# usb_isolated_uart_x2.net
KiCad netlist of a schematic drawn in Altium Designer
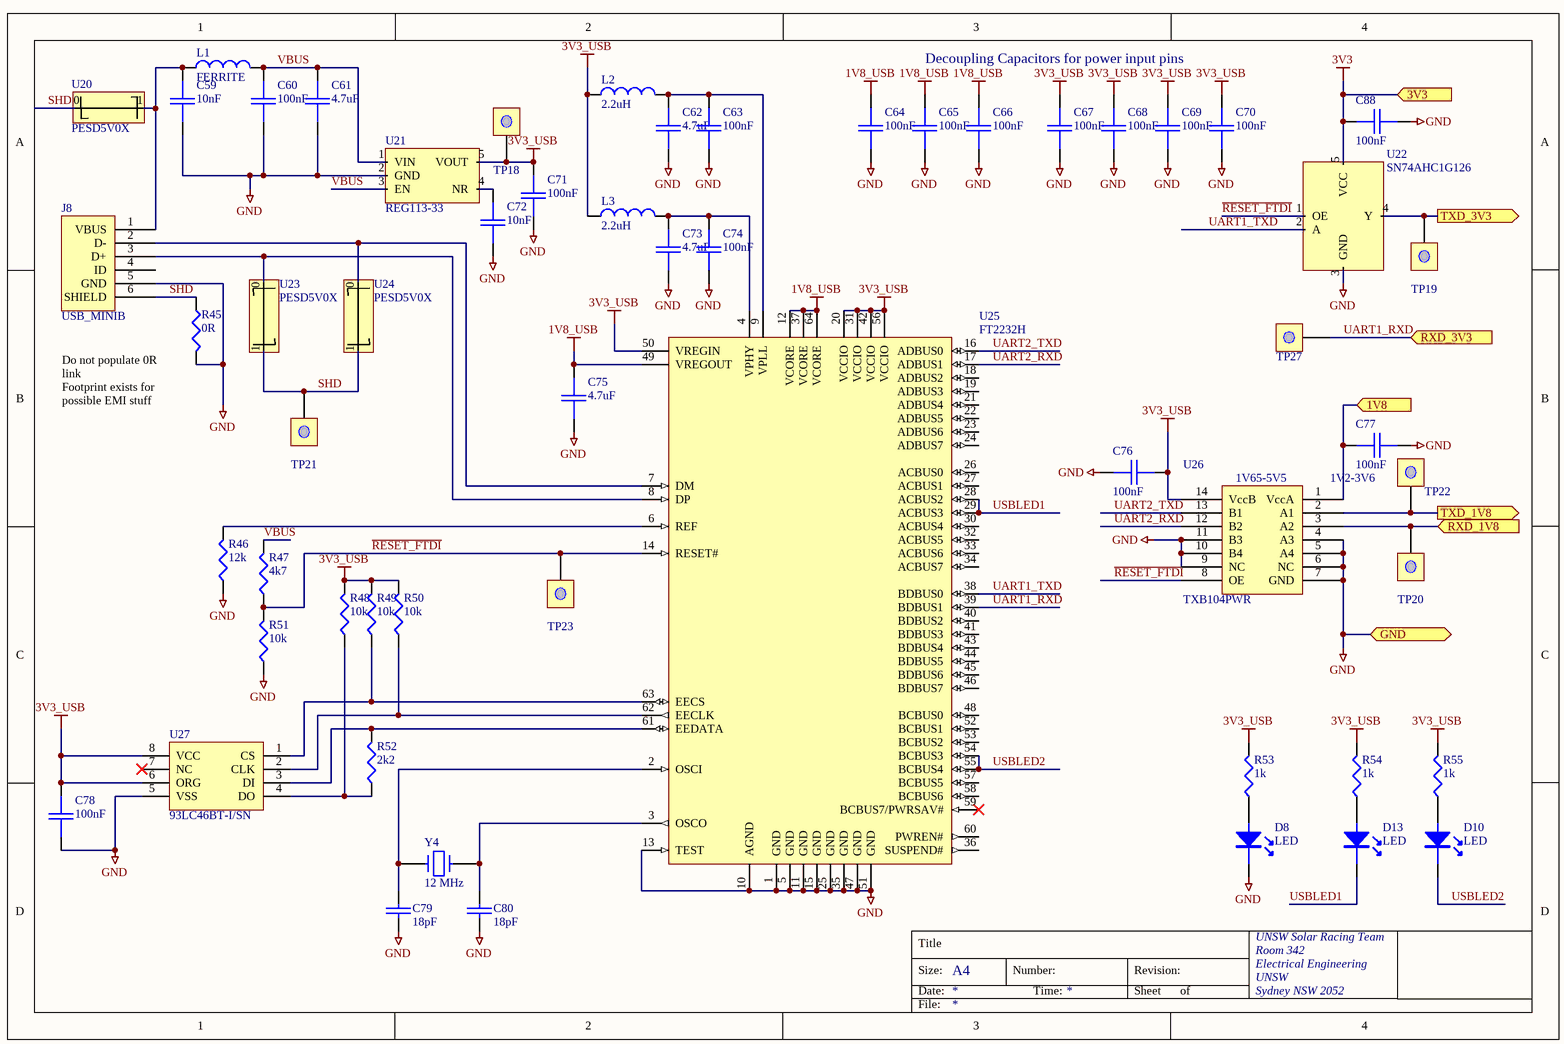
[diagram p0: usb_isolated_uart_x2.SchDoc]

(export (version "E")
  (design (tool "Eeschema 10.0.6"))
  (components
    (comp (ref "C59")
      (value "10nF")
      (footprint "0603")
      (description "Capacitor")
      (libsource (lib "RCLDQ") (part "CAP"))
    )
    (comp (ref "C60")
      (value "100nF")
      (footprint "0603")
      (description "Capacitor")
      (libsource (lib "RCLDQ") (part "CAP"))
    )
    (comp (ref "C61")
      (value "4.7uF")
      (footprint "0603")
      (description "Capacitor")
      (libsource (lib "RCLDQ") (part "CAP"))
    )
    (comp (ref "C62")
      (value "4.7uF")
      (footprint "0603")
      (description "Capacitor")
      (libsource (lib "RCLDQ") (part "CAP"))
    )
    (comp (ref "C63")
      (value "100nF")
      (footprint "0603")
      (description "Capacitor")
      (libsource (lib "RCLDQ") (part "CAP"))
    )
    (comp (ref "C64")
      (value "100nF")
      (footprint "0603")
      (description "Capacitor")
      (libsource (lib "RCLDQ") (part "CAP"))
    )
    (comp (ref "C65")
      (value "100nF")
      (footprint "0603")
      (description "Capacitor")
      (libsource (lib "RCLDQ") (part "CAP"))
    )
    (comp (ref "C66")
      (value "100nF")
      (footprint "0603")
      (description "Capacitor")
      (libsource (lib "RCLDQ") (part "CAP"))
    )
    (comp (ref "C67")
      (value "100nF")
      (footprint "0603")
      (description "Capacitor")
      (libsource (lib "RCLDQ") (part "CAP"))
    )
    (comp (ref "C68")
      (value "100nF")
      (footprint "0603")
      (description "Capacitor")
      (libsource (lib "RCLDQ") (part "CAP"))
    )
    (comp (ref "C69")
      (value "100nF")
      (footprint "0603")
      (description "Capacitor")
      (libsource (lib "RCLDQ") (part "CAP"))
    )
    (comp (ref "C70")
      (value "100nF")
      (footprint "0603")
      (description "Capacitor")
      (libsource (lib "RCLDQ") (part "CAP"))
    )
    (comp (ref "C71")
      (value "100nF")
      (footprint "0603")
      (description "Capacitor")
      (libsource (lib "RCLDQ") (part "CAP"))
    )
    (comp (ref "C72")
      (value "10nF")
      (footprint "0603")
      (description "Capacitor")
      (libsource (lib "RCLDQ") (part "CAP"))
    )
    (comp (ref "C73")
      (value "4.7uF")
      (footprint "0603")
      (description "Capacitor")
      (libsource (lib "RCLDQ") (part "CAP"))
    )
    (comp (ref "C74")
      (value "100nF")
      (footprint "0603")
      (description "Capacitor")
      (libsource (lib "RCLDQ") (part "CAP"))
    )
    (comp (ref "C75")
      (value "4.7uF")
      (footprint "0603")
      (description "Capacitor")
      (libsource (lib "RCLDQ") (part "CAP"))
    )
    (comp (ref "C76")
      (value "100nF")
      (footprint "0603")
      (description "Capacitor")
      (libsource (lib "RCLDQ") (part "CAP"))
    )
    (comp (ref "C77")
      (value "100nF")
      (footprint "0603")
      (description "Capacitor")
      (libsource (lib "RCLDQ") (part "CAP"))
    )
    (comp (ref "C78")
      (value "100nF")
      (footprint "0603")
      (description "Capacitor")
      (libsource (lib "RCLDQ") (part "CAP"))
    )
    (comp (ref "C79")
      (value "18pF")
      (footprint "0603")
      (description "Capacitor")
      (libsource (lib "*") (part "CAP"))
    )
    (comp (ref "C80")
      (value "18pF")
      (footprint "0603")
      (description "Capacitor")
      (libsource (lib "*") (part "CAP"))
    )
    (comp (ref "C88")
      (value "100nF")
      (footprint "0603")
      (description "Capacitor")
      (libsource (lib "RCLDQ") (part "CAP"))
    )
    (comp (ref "D8") (value "LED") (footprint "0805LED") (libsource (lib "RCLDQ") (part "LED")))
    (comp (ref "D10") (value "LED") (footprint "0805LED") (libsource (lib "RCLDQ") (part "LED")))
    (comp (ref "D13") (value "LED") (footprint "0805LED") (libsource (lib "RCLDQ") (part "LED")))
    (comp (ref "J8")
      (value "USB_MINIB")
      (footprint "USB_MINIB")
      (description "USB Mini B Connector")
      (libsource (lib "sion") (part "USB_miniB_SMT"))
    )
    (comp (ref "L1")
      (value "FERRITE")
      (footprint "0603")
      (description "Inductor")
      (libsource (lib "RCLDQ") (part "INDUCTOR"))
    )
    (comp (ref "L2")
      (value "2.2uH")
      (footprint "1210")
      (description "Inductor")
      (libsource (lib "RCLDQ") (part "INDUCTOR"))
    )
    (comp (ref "L3")
      (value "2.2uH")
      (footprint "1210")
      (description "Inductor")
      (libsource (lib "RCLDQ") (part "INDUCTOR"))
    )
    (comp (ref "R45")
      (value "0R")
      (footprint "1206")
      (description "Resistor")
      (libsource (lib "RCLDQ") (part "RES1"))
    )
    (comp (ref "R46")
      (value "12k")
      (footprint "0603")
      (description "Resistor")
      (libsource (lib "RCLDQ") (part "RES1"))
    )
    (comp (ref "R47")
      (value "4k7")
      (footprint "0603")
      (description "Resistor")
      (libsource (lib "RCLDQ") (part "RES1"))
    )
    (comp (ref "R48")
      (value "10k")
      (footprint "0603")
      (description "Resistor")
      (libsource (lib "RCLDQ") (part "RES1"))
    )
    (comp (ref "R49")
      (value "10k")
      (footprint "0603")
      (description "Resistor")
      (libsource (lib "RCLDQ") (part "RES1"))
    )
    (comp (ref "R50")
      (value "10k")
      (footprint "0603")
      (description "Resistor")
      (libsource (lib "RCLDQ") (part "RES1"))
    )
    (comp (ref "R51")
      (value "10k")
      (footprint "0603")
      (description "Resistor")
      (libsource (lib "RCLDQ") (part "RES1"))
    )
    (comp (ref "R52")
      (value "2k2")
      (footprint "0603")
      (description "Resistor")
      (libsource (lib "RCLDQ") (part "RES1"))
    )
    (comp (ref "R53")
      (value "1k")
      (footprint "0603")
      (description "Resistor")
      (libsource (lib "RCLDQ") (part "RES1"))
    )
    (comp (ref "R54")
      (value "1k")
      (footprint "0603")
      (description "Resistor")
      (libsource (lib "RCLDQ") (part "RES1"))
    )
    (comp (ref "R55")
      (value "1k")
      (footprint "0603")
      (description "Resistor")
      (libsource (lib "RCLDQ") (part "RES1"))
    )
    (comp (ref "TP18")
      (value "3V3USB")
      (footprint "TESTPOINT")
      (description "TEST POINT")
      (libsource (lib "") (part "TEST_2"))
    )
    (comp (ref "TP19")
      (value "TXD3V3")
      (footprint "TESTPOINT")
      (description "TEST POINT")
      (libsource (lib "Miscellaneous") (part "TEST"))
    )
    (comp (ref "TP20")
      (value "RXD1V8")
      (footprint "TESTPOINT")
      (description "TEST POINT")
      (libsource (lib "Miscellaneous") (part "TEST"))
    )
    (comp (ref "TP21")
      (value "SHD")
      (footprint "TESTPOINT")
      (description "TEST POINT")
      (libsource (lib "Miscellaneous") (part "TEST"))
    )
    (comp (ref "TP22")
      (value "TXD1V8")
      (footprint "TESTPOINT")
      (description "TEST POINT")
      (libsource (lib "") (part "TEST_2"))
    )
    (comp (ref "TP23")
      (value "FTDI_RST")
      (footprint "TESTPOINT")
      (description "TEST POINT")
      (libsource (lib "Miscellaneous") (part "TEST"))
    )
    (comp (ref "TP27")
      (value "RXD3V3")
      (footprint "TESTPOINT")
      (description "TEST POINT")
      (libsource (lib "") (part "TEST_1"))
    )
    (comp (ref "U20")
      (value "PESD5V0X")
      (footprint "SOD323")
      (description "Ultra low capacitance bidirectional ESD protection diodes")
      (libsource (lib "gumstix") (part "PESD5V0X"))
    )
    (comp (ref "U21")
      (value "REG113-33")
      (footprint "SOT23-5")
      (description "400mA Low-Dropout Regulator")
      (libsource (lib "gumstix") (part "REG113-33"))
    )
    (comp (ref "U22")
      (value "SN74AHC1G126")
      (footprint "SOT23-5")
      (description "Single Bus Buffer Gate with 3 State Output")
      (libsource (lib "gumstix") (part "SN74AHC1G126"))
    )
    (comp (ref "U23")
      (value "PESD5V0X")
      (footprint "SOD323")
      (description "Ultra low capacitance bidirectional ESD protection diodes")
      (libsource (lib "") (part "PESD5V0X_1"))
    )
    (comp (ref "U24")
      (value "PESD5V0X")
      (footprint "SOD323")
      (description "Ultra low capacitance bidirectional ESD protection diodes")
      (libsource (lib "") (part "PESD5V0X_1"))
    )
    (comp (ref "U25")
      (value "FT2232H")
      (footprint "QFP64")
      (description "Dual USB to UART/FIFO")
      (libsource (lib "sion") (part "FT2232H"))
    )
    (comp (ref "U26")
      (value "TXB104PWR")
      (footprint "TSSOP14-L")
      (description "4 bit bidirectional auto direction sense level translator")
      (libsource (lib "sion") (part "TXB0104PWR"))
    )
    (comp (ref "U27")
      (value "93LC46BT-I/SN")
      (footprint "SO8")
      (description "Serial EEPROM")
      (libsource (lib "sion") (part "93LC46BT-I/SN"))
    )
    (comp (ref "Y4")
      (value "12 MHz")
      (footprint "HC49/4H")
      (description "Crystal")
      (libsource (lib "*") (part "CRYSTAL"))
    )
  )
  (nets
    (net (code "1") (name "/1V8") (class "Default")
      (node (ref "C77") (pin "1") (pinfunction "1_1") (pintype "passive"))
      (node (ref "U26") (pin "1") (pinfunction "VccA_1") (pintype "power_in"))
    )
    (net (code "2") (name "/RESET_FTDI") (class "Default")
      (node (ref "R47") (pin "1") (pinfunction "1_1") (pintype "passive"))
      (node (ref "R51") (pin "2") (pinfunction "2_2") (pintype "passive"))
      (node (ref "TP23") (pin "0") (pinfunction "TP_0") (pintype "passive"))
      (node (ref "U22") (pin "1") (pinfunction "OE_1") (pintype "passive"))
      (node (ref "U25") (pin "14") (pinfunction "RESET#_14") (pintype "input"))
      (node (ref "U26") (pin "8") (pinfunction "OE_8") (pintype "passive"))
    )
    (net (code "3") (name "/RXD_1V8") (class "Default")
      (node (ref "TP20") (pin "0") (pinfunction "TP_0") (pintype "passive"))
      (node (ref "U26") (pin "3") (pinfunction "A2_3") (pintype "passive"))
    )
    (net (code "4") (name "/SHD") (class "Default")
      (node (ref "J8") (pin "6") (pinfunction "SHIELD_6") (pintype "passive"))
      (node (ref "R45") (pin "1") (pinfunction "1_1") (pintype "passive"))
      (node (ref "TP21") (pin "0") (pinfunction "TP_0") (pintype "passive"))
      (node (ref "U20") (pin "0") (pintype "passive"))
      (node (ref "U23") (pin "1") (pintype "passive"))
      (node (ref "U24") (pin "1") (pintype "passive"))
    )
    (net (code "5") (name "/TXD_1V8") (class "Default")
      (node (ref "TP22") (pin "0") (pinfunction "TP_0") (pintype "passive"))
      (node (ref "U26") (pin "2") (pinfunction "A1_2") (pintype "passive"))
    )
    (net (code "6") (name "/TXD_3V3") (class "Default")
      (node (ref "TP19") (pin "0") (pinfunction "TP_0") (pintype "passive"))
      (node (ref "U22") (pin "4") (pinfunction "Y_4") (pintype "passive"))
    )
    (net (code "7") (name "/UART1_RXD") (class "Default")
      (node (ref "TP27") (pin "0") (pinfunction "TP_0") (pintype "passive"))
      (node (ref "U25") (pin "39") (pinfunction "BDBUS1_39") (pintype "bidirectional"))
    )
    (net (code "8") (name "/UART1_TXD") (class "Default")
      (node (ref "U22") (pin "2") (pinfunction "A_2") (pintype "passive"))
      (node (ref "U25") (pin "38") (pinfunction "BDBUS0_38") (pintype "bidirectional"))
    )
    (net (code "9") (name "/UART2_RXD") (class "Default")
      (node (ref "U25") (pin "17") (pinfunction "ADBUS1_17") (pintype "bidirectional"))
      (node (ref "U26") (pin "12") (pinfunction "B2_12") (pintype "passive"))
    )
    (net (code "10") (name "/UART2_TXD") (class "Default")
      (node (ref "U25") (pin "16") (pinfunction "ADBUS0_16") (pintype "bidirectional"))
      (node (ref "U26") (pin "13") (pinfunction "B1_13") (pintype "passive"))
    )
    (net (code "11") (name "/USBLED1") (class "Default")
      (node (ref "D13") (pin "K") (pinfunction "K_K") (pintype "passive"))
      (node (ref "U25") (pin "28") (pinfunction "ACBUS2_28") (pintype "bidirectional"))
      (node (ref "U25") (pin "29") (pinfunction "ACBUS3_29") (pintype "bidirectional"))
    )
    (net (code "12") (name "/USBLED2") (class "Default")
      (node (ref "D10") (pin "K") (pinfunction "K_K") (pintype "passive"))
      (node (ref "U25") (pin "54") (pinfunction "BCBUS3_54") (pintype "bidirectional"))
      (node (ref "U25") (pin "55") (pinfunction "BCBUS4_55") (pintype "bidirectional"))
    )
    (net (code "13") (name "/VBUS") (class "Default")
      (node (ref "C60") (pin "1") (pinfunction "1_1") (pintype "passive"))
      (node (ref "C61") (pin "1") (pinfunction "1_1") (pintype "passive"))
      (node (ref "L1") (pin "2") (pinfunction "2_2") (pintype "passive"))
      (node (ref "R47") (pin "2") (pinfunction "2_2") (pintype "passive"))
      (node (ref "U21") (pin "1") (pinfunction "VIN_1") (pintype "passive"))
      (node (ref "U21") (pin "3") (pinfunction "EN_3") (pintype "passive"))
    )
    (net (code "14") (name "1V8_USB") (class "Default")
      (node (ref "C64") (pin "1") (pinfunction "1_1") (pintype "passive"))
      (node (ref "C65") (pin "1") (pinfunction "1_1") (pintype "passive"))
      (node (ref "C66") (pin "1") (pinfunction "1_1") (pintype "passive"))
      (node (ref "C75") (pin "1") (pinfunction "1_1") (pintype "passive"))
      (node (ref "U25") (pin "12") (pinfunction "VCORE_12") (pintype "power_in"))
      (node (ref "U25") (pin "37") (pinfunction "VCORE_37") (pintype "power_in"))
      (node (ref "U25") (pin "49") (pinfunction "VREGOUT_49") (pintype "power_in"))
      (node (ref "U25") (pin "64") (pinfunction "VCORE_64") (pintype "power_in"))
    )
    (net (code "15") (name "3V3") (class "Default")
      (node (ref "C88") (pin "2") (pinfunction "2_2") (pintype "passive"))
      (node (ref "U22") (pin "5") (pinfunction "VCC_5") (pintype "passive"))
    )
    (net (code "16") (name "3V3_USB") (class "Default")
      (node (ref "C67") (pin "1") (pinfunction "1_1") (pintype "passive"))
      (node (ref "C68") (pin "1") (pinfunction "1_1") (pintype "passive"))
      (node (ref "C69") (pin "1") (pinfunction "1_1") (pintype "passive"))
      (node (ref "C70") (pin "1") (pinfunction "1_1") (pintype "passive"))
      (node (ref "C71") (pin "1") (pinfunction "1_1") (pintype "passive"))
      (node (ref "C76") (pin "2") (pinfunction "2_2") (pintype "passive"))
      (node (ref "C78") (pin "1") (pinfunction "1_1") (pintype "passive"))
      (node (ref "L2") (pin "1") (pinfunction "1_1") (pintype "passive"))
      (node (ref "L3") (pin "1") (pinfunction "1_1") (pintype "passive"))
      (node (ref "R48") (pin "2") (pinfunction "2_2") (pintype "passive"))
      (node (ref "R49") (pin "2") (pinfunction "2_2") (pintype "passive"))
      (node (ref "R50") (pin "2") (pinfunction "2_2") (pintype "passive"))
      (node (ref "R53") (pin "2") (pinfunction "2_2") (pintype "passive"))
      (node (ref "R54") (pin "2") (pinfunction "2_2") (pintype "passive"))
      (node (ref "R55") (pin "2") (pinfunction "2_2") (pintype "passive"))
      (node (ref "TP18") (pin "0") (pinfunction "TP_0") (pintype "passive"))
      (node (ref "U21") (pin "5") (pinfunction "VOUT_5") (pintype "passive"))
      (node (ref "U25") (pin "20") (pinfunction "VCCIO_20") (pintype "power_in"))
      (node (ref "U25") (pin "31") (pinfunction "VCCIO_31") (pintype "power_in"))
      (node (ref "U25") (pin "42") (pinfunction "VCCIO_42") (pintype "power_in"))
      (node (ref "U25") (pin "50") (pinfunction "VREGIN_50") (pintype "power_in"))
      (node (ref "U25") (pin "56") (pinfunction "VCCIO_56") (pintype "power_in"))
      (node (ref "U26") (pin "14") (pinfunction "VccB_14") (pintype "power_in"))
      (node (ref "U27") (pin "6") (pinfunction "ORG_6") (pintype "passive"))
      (node (ref "U27") (pin "8") (pinfunction "VCC_8") (pintype "passive"))
    )
    (net (code "17") (name "GND") (class "Default")
      (node (ref "C59") (pin "1") (pinfunction "1_1") (pintype "passive"))
      (node (ref "C60") (pin "2") (pinfunction "2_2") (pintype "passive"))
      (node (ref "C61") (pin "2") (pinfunction "2_2") (pintype "passive"))
      (node (ref "C62") (pin "2") (pinfunction "2_2") (pintype "passive"))
      (node (ref "C63") (pin "2") (pinfunction "2_2") (pintype "passive"))
      (node (ref "C64") (pin "2") (pinfunction "2_2") (pintype "passive"))
      (node (ref "C65") (pin "2") (pinfunction "2_2") (pintype "passive"))
      (node (ref "C66") (pin "2") (pinfunction "2_2") (pintype "passive"))
      (node (ref "C67") (pin "2") (pinfunction "2_2") (pintype "passive"))
      (node (ref "C68") (pin "2") (pinfunction "2_2") (pintype "passive"))
      (node (ref "C69") (pin "2") (pinfunction "2_2") (pintype "passive"))
      (node (ref "C70") (pin "2") (pinfunction "2_2") (pintype "passive"))
      (node (ref "C71") (pin "2") (pinfunction "2_2") (pintype "passive"))
      (node (ref "C72") (pin "2") (pinfunction "2_2") (pintype "passive"))
      (node (ref "C73") (pin "2") (pinfunction "2_2") (pintype "passive"))
      (node (ref "C74") (pin "2") (pinfunction "2_2") (pintype "passive"))
      (node (ref "C75") (pin "2") (pinfunction "2_2") (pintype "passive"))
      (node (ref "C76") (pin "1") (pinfunction "1_1") (pintype "passive"))
      (node (ref "C77") (pin "2") (pinfunction "2_2") (pintype "passive"))
      (node (ref "C78") (pin "2") (pinfunction "2_2") (pintype "passive"))
      (node (ref "C79") (pin "2") (pinfunction "2_2") (pintype "passive"))
      (node (ref "C80") (pin "2") (pinfunction "2_2") (pintype "passive"))
      (node (ref "C88") (pin "1") (pinfunction "1_1") (pintype "passive"))
      (node (ref "D8") (pin "K") (pinfunction "K_K") (pintype "passive"))
      (node (ref "J8") (pin "5") (pinfunction "GND_5") (pintype "passive"))
      (node (ref "R45") (pin "2") (pinfunction "2_2") (pintype "passive"))
      (node (ref "R46") (pin "1") (pinfunction "1_1") (pintype "passive"))
      (node (ref "R51") (pin "1") (pinfunction "1_1") (pintype "passive"))
      (node (ref "U21") (pin "2") (pinfunction "GND_2") (pintype "passive"))
      (node (ref "U22") (pin "3") (pinfunction "GND_3") (pintype "passive"))
      (node (ref "U25") (pin "1") (pinfunction "GND_1") (pintype "power_in"))
      (node (ref "U25") (pin "10") (pinfunction "AGND_10") (pintype "power_in"))
      (node (ref "U25") (pin "11") (pinfunction "GND_11") (pintype "power_in"))
      (node (ref "U25") (pin "13") (pinfunction "TEST_13") (pintype "input"))
      (node (ref "U25") (pin "15") (pinfunction "GND_15") (pintype "power_in"))
      (node (ref "U25") (pin "25") (pinfunction "GND_25") (pintype "power_in"))
      (node (ref "U25") (pin "35") (pinfunction "GND_35") (pintype "power_in"))
      (node (ref "U25") (pin "47") (pinfunction "GND_47") (pintype "power_in"))
      (node (ref "U25") (pin "5") (pinfunction "GND_5") (pintype "power_in"))
      (node (ref "U25") (pin "51") (pinfunction "GND_51") (pintype "power_in"))
      (node (ref "U26") (pin "10") (pinfunction "B4_10") (pintype "passive"))
      (node (ref "U26") (pin "11") (pinfunction "B3_11") (pintype "passive"))
      (node (ref "U26") (pin "4") (pinfunction "A3_4") (pintype "passive"))
      (node (ref "U26") (pin "5") (pinfunction "A4_5") (pintype "passive"))
      (node (ref "U26") (pin "6") (pinfunction "NC_6") (pintype "passive"))
      (node (ref "U26") (pin "7") (pinfunction "GND_7") (pintype "power_in"))
      (node (ref "U26") (pin "9") (pinfunction "NC_9") (pintype "passive"))
      (node (ref "U27") (pin "5") (pinfunction "VSS_5") (pintype "passive"))
    )
    (net (code "18") (name "Net-(D8-PadA)") (class "Default")
      (node (ref "D8") (pin "A") (pinfunction "A_A") (pintype "passive"))
      (node (ref "R53") (pin "1") (pinfunction "1_1") (pintype "passive"))
    )
    (net (code "19") (name "Net-(D10-PadA)") (class "Default")
      (node (ref "D10") (pin "A") (pinfunction "A_A") (pintype "passive"))
      (node (ref "R55") (pin "1") (pinfunction "1_1") (pintype "passive"))
    )
    (net (code "20") (name "Net-(D13-PadA)") (class "Default")
      (node (ref "D13") (pin "A") (pinfunction "A_A") (pintype "passive"))
      (node (ref "R54") (pin "1") (pinfunction "1_1") (pintype "passive"))
    )
    (net (code "21") (name "Net-(J8-D+)") (class "Default")
      (node (ref "J8") (pin "3") (pinfunction "D+_3") (pintype "passive"))
      (node (ref "U23") (pin "0") (pintype "passive"))
      (node (ref "U25") (pin "8") (pinfunction "DP_8") (pintype "input"))
    )
    (net (code "22") (name "Net-(J8-D-)") (class "Default")
      (node (ref "J8") (pin "2") (pinfunction "D-_2") (pintype "passive"))
      (node (ref "U24") (pin "0") (pintype "passive"))
      (node (ref "U25") (pin "7") (pinfunction "DM_7") (pintype "input"))
    )
    (net (code "23") (name "Net-(J8-VBUS)") (class "Default")
      (node (ref "C59") (pin "2") (pinfunction "2_2") (pintype "passive"))
      (node (ref "J8") (pin "1") (pinfunction "VBUS_1") (pintype "passive"))
      (node (ref "L1") (pin "1") (pinfunction "1_1") (pintype "passive"))
      (node (ref "U20") (pin "1") (pintype "passive"))
    )
    (net (code "24") (name "Net-(U21-NR)") (class "Default")
      (node (ref "C72") (pin "1") (pinfunction "1_1") (pintype "passive"))
      (node (ref "U21") (pin "4") (pinfunction "NR_4") (pintype "passive"))
    )
    (net (code "25") (name "Net-(U25-EECLK)") (class "Default")
      (node (ref "R50") (pin "1") (pinfunction "1_1") (pintype "passive"))
      (node (ref "U25") (pin "62") (pinfunction "EECLK_62") (pintype "output"))
      (node (ref "U27") (pin "2") (pinfunction "CLK_2") (pintype "passive"))
    )
    (net (code "26") (name "Net-(U25-EECS)") (class "Default")
      (node (ref "R49") (pin "1") (pinfunction "1_1") (pintype "passive"))
      (node (ref "U25") (pin "63") (pinfunction "EECS_63") (pintype "bidirectional"))
      (node (ref "U27") (pin "1") (pinfunction "CS_1") (pintype "passive"))
    )
    (net (code "27") (name "Net-(U25-EEDATA)") (class "Default")
      (node (ref "R52") (pin "2") (pinfunction "2_2") (pintype "passive"))
      (node (ref "U25") (pin "61") (pinfunction "EEDATA_61") (pintype "bidirectional"))
      (node (ref "U27") (pin "3") (pinfunction "DI_3") (pintype "passive"))
    )
    (net (code "28") (name "Net-(U25-OSCI)") (class "Default")
      (node (ref "C79") (pin "1") (pinfunction "1_1") (pintype "passive"))
      (node (ref "U25") (pin "2") (pinfunction "OSCI_2") (pintype "input"))
      (node (ref "Y4") (pin "2") (pinfunction "2_2") (pintype "passive"))
    )
    (net (code "29") (name "Net-(U25-OSCO)") (class "Default")
      (node (ref "C80") (pin "1") (pinfunction "1_1") (pintype "passive"))
      (node (ref "U25") (pin "3") (pinfunction "OSCO_3") (pintype "output"))
      (node (ref "Y4") (pin "1") (pinfunction "1_1") (pintype "passive"))
    )
    (net (code "30") (name "Net-(U25-REF)") (class "Default")
      (node (ref "R46") (pin "2") (pinfunction "2_2") (pintype "passive"))
      (node (ref "U25") (pin "6") (pinfunction "REF_6") (pintype "input"))
    )
    (net (code "31") (name "Net-(U25-VPHY)") (class "Default")
      (node (ref "C73") (pin "1") (pinfunction "1_1") (pintype "passive"))
      (node (ref "C74") (pin "1") (pinfunction "1_1") (pintype "passive"))
      (node (ref "L3") (pin "2") (pinfunction "2_2") (pintype "passive"))
      (node (ref "U25") (pin "4") (pinfunction "VPHY_4") (pintype "power_in"))
    )
    (net (code "32") (name "Net-(U25-VPLL)") (class "Default")
      (node (ref "C62") (pin "1") (pinfunction "1_1") (pintype "passive"))
      (node (ref "C63") (pin "1") (pinfunction "1_1") (pintype "passive"))
      (node (ref "L2") (pin "2") (pinfunction "2_2") (pintype "passive"))
      (node (ref "U25") (pin "9") (pinfunction "VPLL_9") (pintype "power_in"))
    )
    (net (code "33") (name "Net-(U27-DO)") (class "Default")
      (node (ref "R48") (pin "1") (pinfunction "1_1") (pintype "passive"))
      (node (ref "R52") (pin "1") (pinfunction "1_1") (pintype "passive"))
      (node (ref "U27") (pin "4") (pinfunction "DO_4") (pintype "passive"))
    )
    (net (code "34") (name "unconnected-(J8-ID-Pad4)") (class "Default")
      (node (ref "J8") (pin "4") (pinfunction "ID_4") (pintype "passive"))
    )
    (net (code "35") (name "unconnected-(U25-ACBUS0-Pad26)") (class "Default")
      (node (ref "U25") (pin "26") (pinfunction "ACBUS0_26") (pintype "bidirectional"))
    )
    (net (code "36") (name "unconnected-(U25-ACBUS1-Pad27)") (class "Default")
      (node (ref "U25") (pin "27") (pinfunction "ACBUS1_27") (pintype "bidirectional"))
    )
    (net (code "37") (name "unconnected-(U25-ACBUS4-Pad30)") (class "Default")
      (node (ref "U25") (pin "30") (pinfunction "ACBUS4_30") (pintype "bidirectional"))
    )
    (net (code "38") (name "unconnected-(U25-ACBUS5-Pad32)") (class "Default")
      (node (ref "U25") (pin "32") (pinfunction "ACBUS5_32") (pintype "bidirectional"))
    )
    (net (code "39") (name "unconnected-(U25-ACBUS6-Pad33)") (class "Default")
      (node (ref "U25") (pin "33") (pinfunction "ACBUS6_33") (pintype "bidirectional"))
    )
    (net (code "40") (name "unconnected-(U25-ACBUS7-Pad34)") (class "Default")
      (node (ref "U25") (pin "34") (pinfunction "ACBUS7_34") (pintype "bidirectional"))
    )
    (net (code "41") (name "unconnected-(U25-ADBUS2-Pad18)") (class "Default")
      (node (ref "U25") (pin "18") (pinfunction "ADBUS2_18") (pintype "bidirectional"))
    )
    (net (code "42") (name "unconnected-(U25-ADBUS3-Pad19)") (class "Default")
      (node (ref "U25") (pin "19") (pinfunction "ADBUS3_19") (pintype "bidirectional"))
    )
    (net (code "43") (name "unconnected-(U25-ADBUS4-Pad21)") (class "Default")
      (node (ref "U25") (pin "21") (pinfunction "ADBUS4_21") (pintype "bidirectional"))
    )
    (net (code "44") (name "unconnected-(U25-ADBUS5-Pad22)") (class "Default")
      (node (ref "U25") (pin "22") (pinfunction "ADBUS5_22") (pintype "bidirectional"))
    )
    (net (code "45") (name "unconnected-(U25-ADBUS6-Pad23)") (class "Default")
      (node (ref "U25") (pin "23") (pinfunction "ADBUS6_23") (pintype "bidirectional"))
    )
    (net (code "46") (name "unconnected-(U25-ADBUS7-Pad24)") (class "Default")
      (node (ref "U25") (pin "24") (pinfunction "ADBUS7_24") (pintype "bidirectional"))
    )
    (net (code "47") (name "unconnected-(U25-BCBUS0-Pad48)") (class "Default")
      (node (ref "U25") (pin "48") (pinfunction "BCBUS0_48") (pintype "bidirectional"))
    )
    (net (code "48") (name "unconnected-(U25-BCBUS1-Pad52)") (class "Default")
      (node (ref "U25") (pin "52") (pinfunction "BCBUS1_52") (pintype "bidirectional"))
    )
    (net (code "49") (name "unconnected-(U25-BCBUS2-Pad53)") (class "Default")
      (node (ref "U25") (pin "53") (pinfunction "BCBUS2_53") (pintype "bidirectional"))
    )
    (net (code "50") (name "unconnected-(U25-BCBUS5-Pad57)") (class "Default")
      (node (ref "U25") (pin "57") (pinfunction "BCBUS5_57") (pintype "bidirectional"))
    )
    (net (code "51") (name "unconnected-(U25-BCBUS6-Pad58)") (class "Default")
      (node (ref "U25") (pin "58") (pinfunction "BCBUS6_58") (pintype "bidirectional"))
    )
    (net (code "52") (name "unconnected-(U25-BCBUS7{slash}PWRSAV#-Pad59)") (class "Default")
      (node (ref "U25") (pin "59") (pinfunction "BCBUS7/PWRSAV#_59") (pintype "input+no_connect"))
    )
    (net (code "53") (name "unconnected-(U25-BDBUS2-Pad40)") (class "Default")
      (node (ref "U25") (pin "40") (pinfunction "BDBUS2_40") (pintype "bidirectional"))
    )
    (net (code "54") (name "unconnected-(U25-BDBUS3-Pad41)") (class "Default")
      (node (ref "U25") (pin "41") (pinfunction "BDBUS3_41") (pintype "bidirectional"))
    )
    (net (code "55") (name "unconnected-(U25-BDBUS4-Pad43)") (class "Default")
      (node (ref "U25") (pin "43") (pinfunction "BDBUS4_43") (pintype "bidirectional"))
    )
    (net (code "56") (name "unconnected-(U25-BDBUS5-Pad44)") (class "Default")
      (node (ref "U25") (pin "44") (pinfunction "BDBUS5_44") (pintype "bidirectional"))
    )
    (net (code "57") (name "unconnected-(U25-BDBUS6-Pad45)") (class "Default")
      (node (ref "U25") (pin "45") (pinfunction "BDBUS6_45") (pintype "bidirectional"))
    )
    (net (code "58") (name "unconnected-(U25-BDBUS7-Pad46)") (class "Default")
      (node (ref "U25") (pin "46") (pinfunction "BDBUS7_46") (pintype "bidirectional"))
    )
    (net (code "59") (name "unconnected-(U25-PWREN#-Pad60)") (class "Default")
      (node (ref "U25") (pin "60") (pinfunction "PWREN#_60") (pintype "output"))
    )
    (net (code "60") (name "unconnected-(U25-SUSPEND#-Pad36)") (class "Default")
      (node (ref "U25") (pin "36") (pinfunction "SUSPEND#_36") (pintype "output"))
    )
    (net (code "61") (name "unconnected-(U27-NC-Pad7)") (class "Default")
      (node (ref "U27") (pin "7") (pinfunction "NC_7") (pintype "passive+no_connect"))
    )
  )
)
